# eb-1.net
KiCad netlist of a schematic drawn in EAGLE
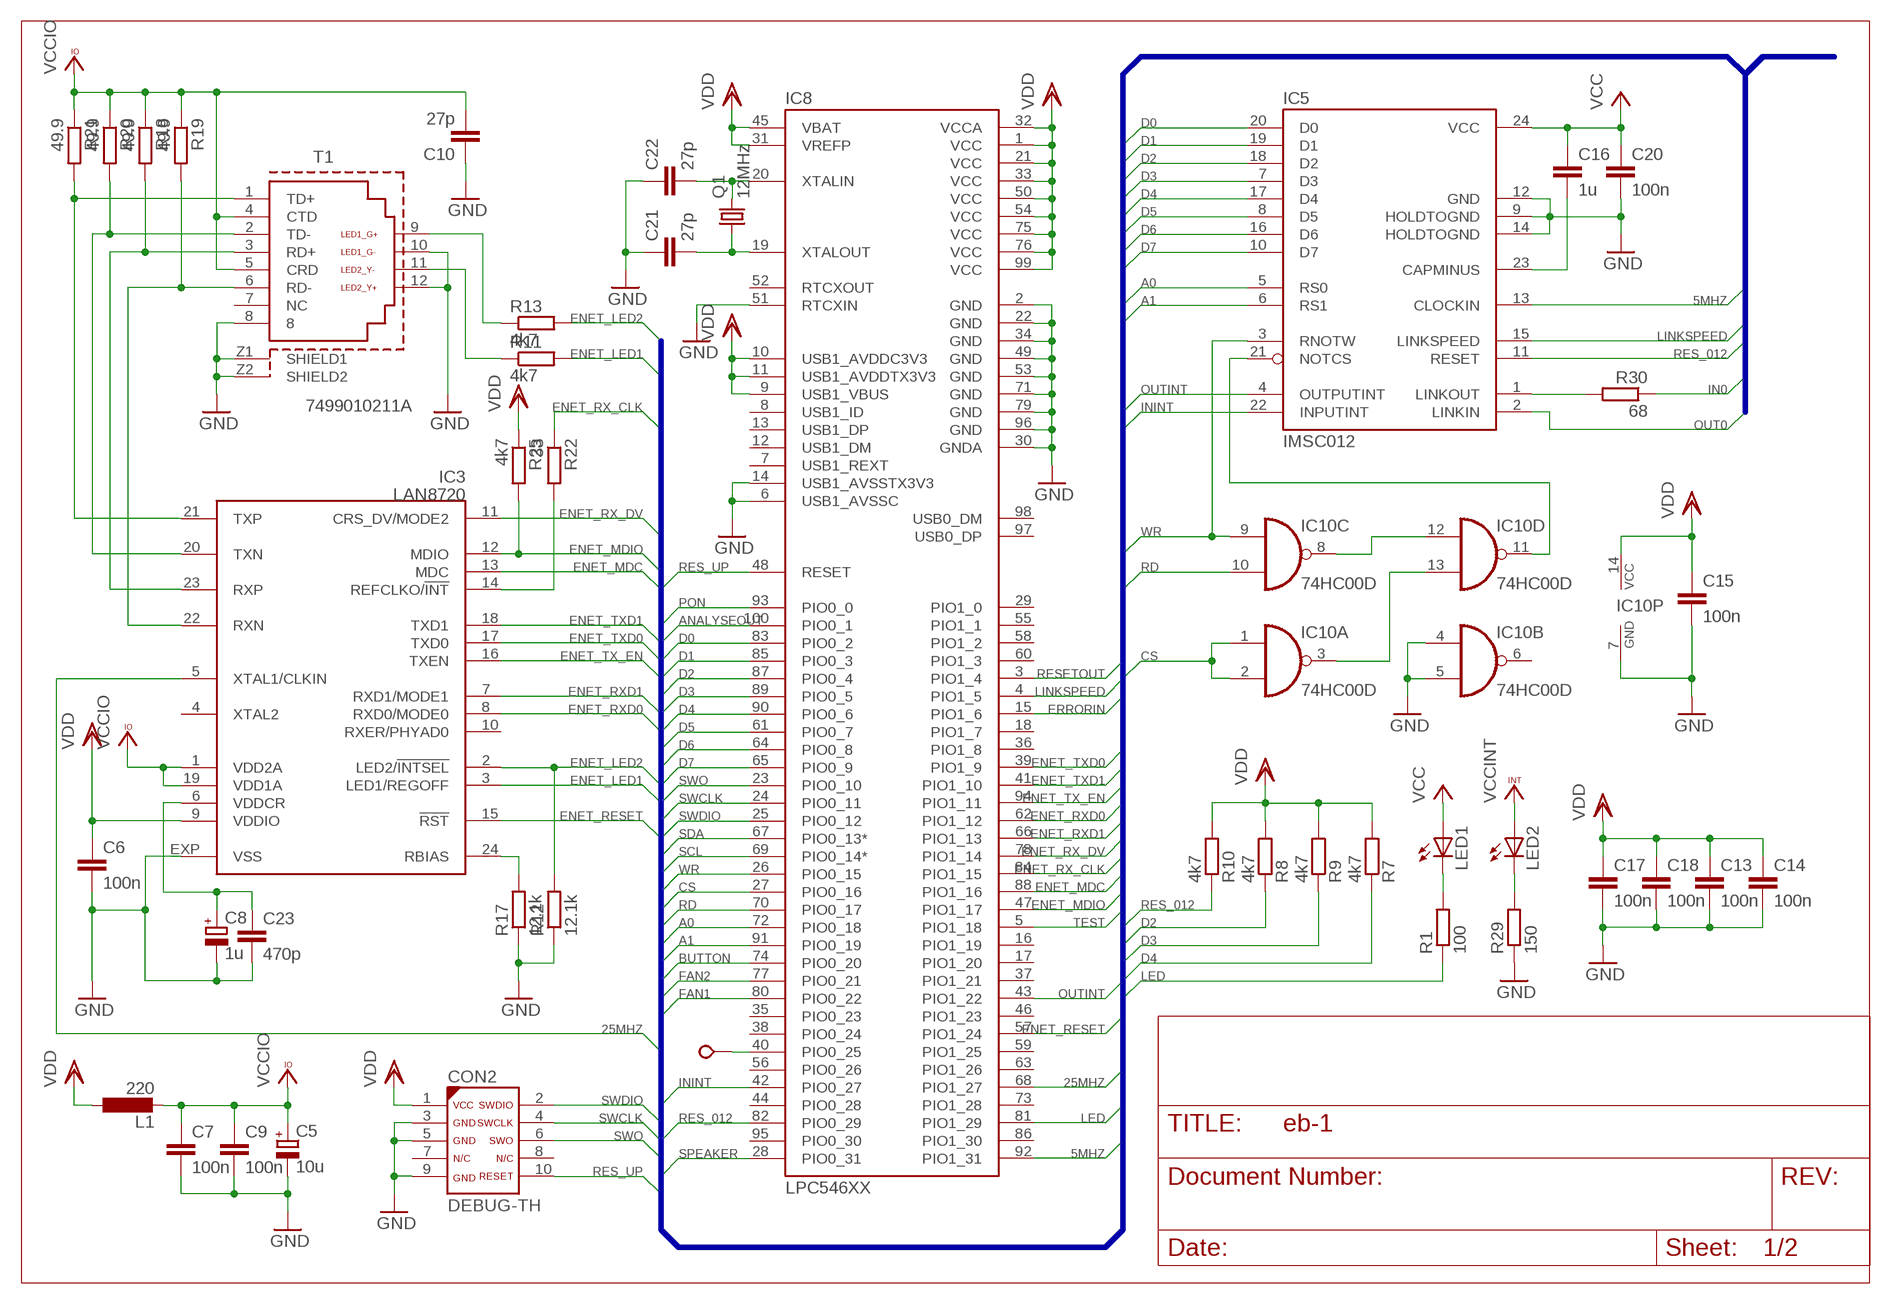
[diagram p0: schematic, sheet 1]
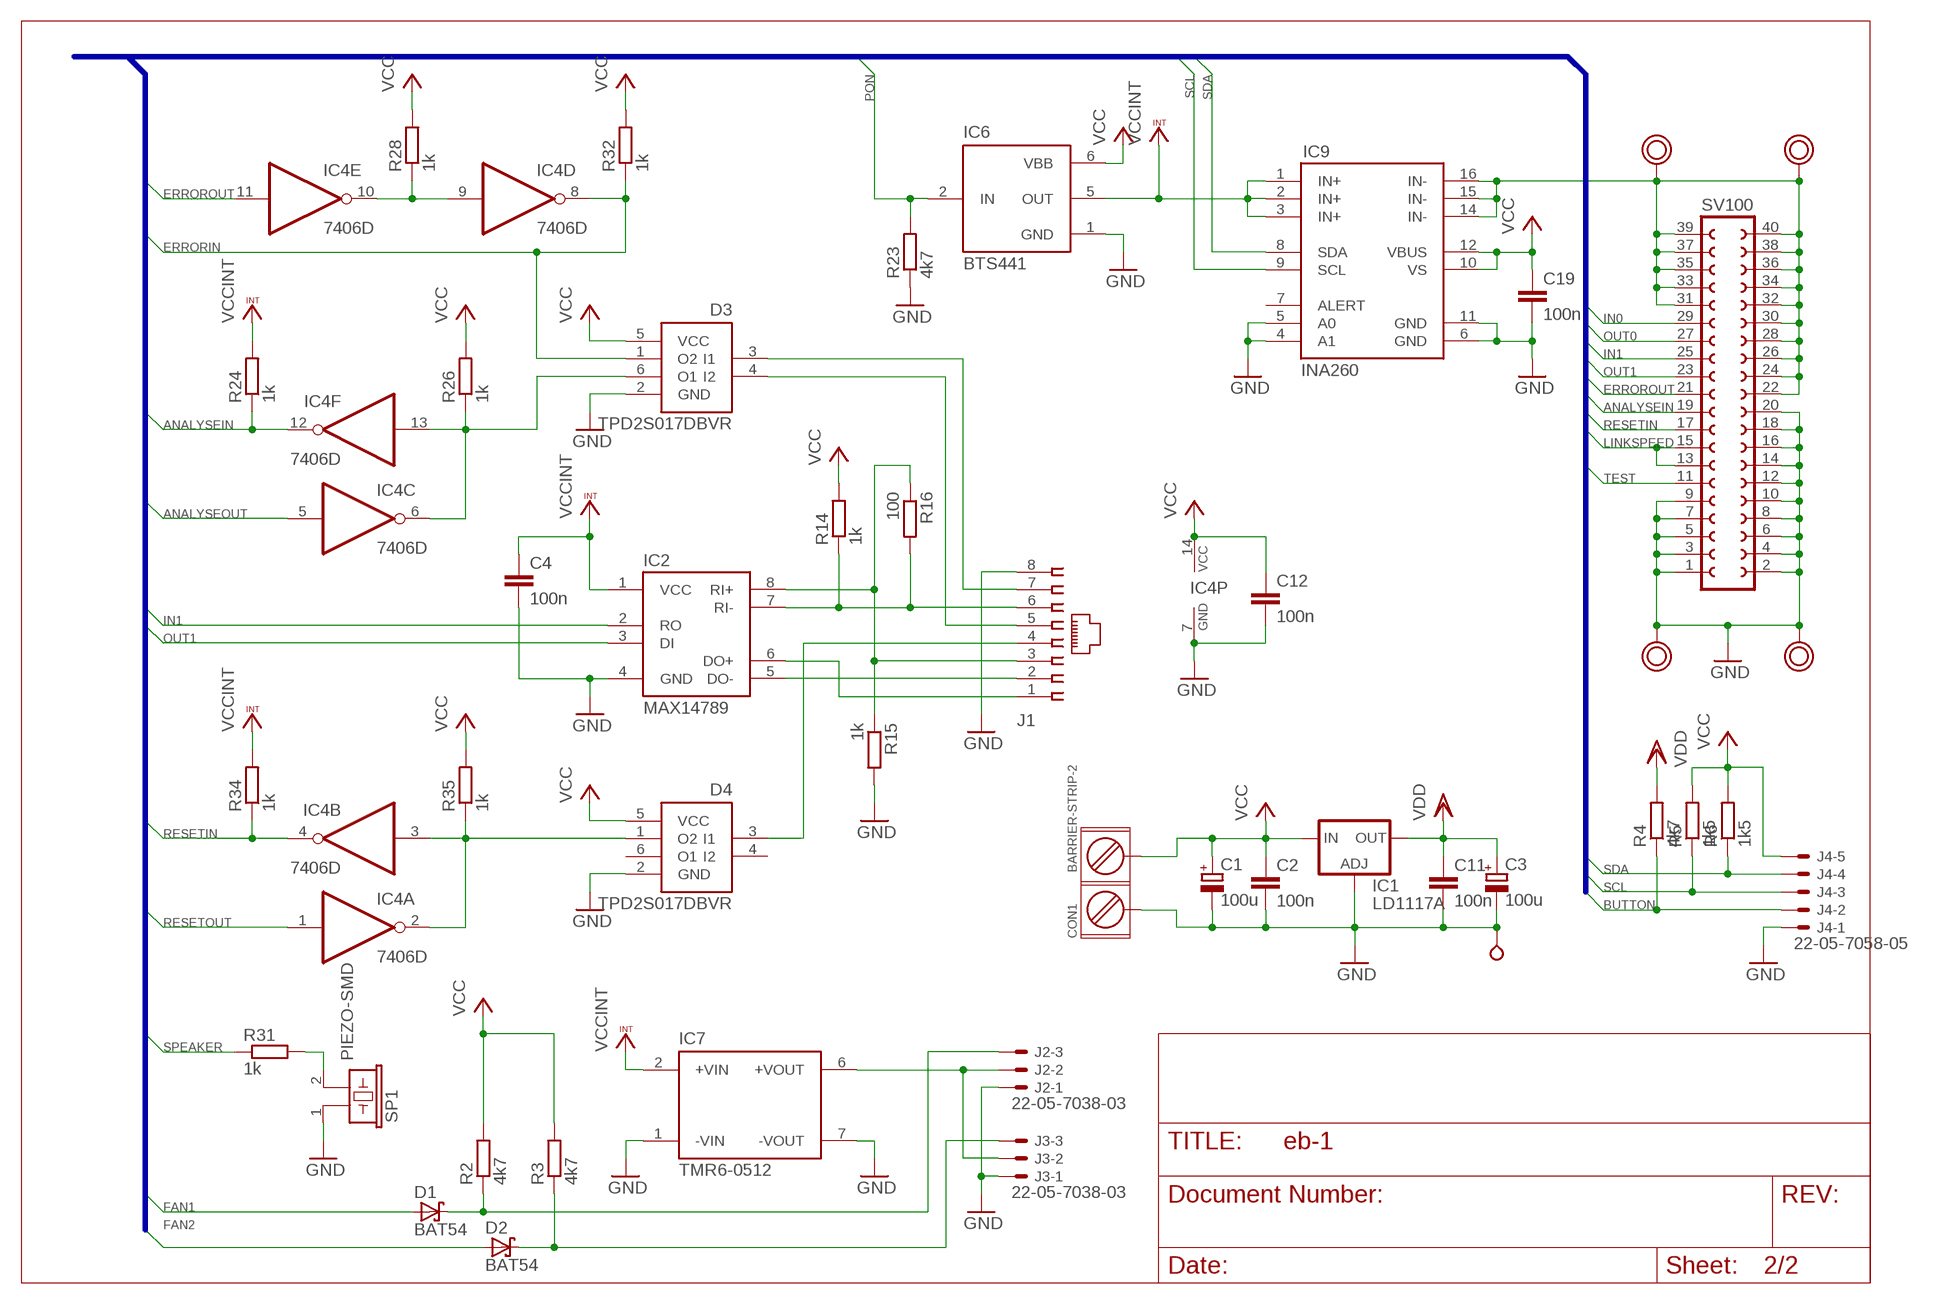
[diagram p1: schematic, sheet 2]

(export (version "E")
  (design (tool "Eeschema 10.0.6"))
  (components
    (comp (ref "C1")
      (value "100u")
      (footprint "eagle-import:SMC_B")
      (libsource (lib "eagle-import") (part "CPOL-EUSMCB"))
    )
    (comp (ref "C2")
      (value "100n")
      (footprint "eagle-import:C1206")
      (libsource (lib "eagle-import") (part "C-EUC1206"))
    )
    (comp (ref "C3")
      (value "100u")
      (footprint "eagle-import:SMC_B")
      (libsource (lib "eagle-import") (part "CPOL-EUSMCB"))
    )
    (comp (ref "C4")
      (value "100n")
      (footprint "eagle-import:C1206")
      (libsource (lib "eagle-import") (part "C-EUC1206"))
    )
    (comp (ref "C11")
      (value "100n")
      (footprint "eagle-import:C1206")
      (libsource (lib "eagle-import") (part "C-EUC1206"))
    )
    (comp (ref "C12")
      (value "100n")
      (footprint "eagle-import:C1206")
      (libsource (lib "eagle-import") (part "C-EUC1206"))
    )
    (comp (ref "C19")
      (value "100n")
      (footprint "eagle-import:C1206")
      (libsource (lib "eagle-import") (part "C-EUC1206"))
    )
    (comp (ref "CON1")
      (value "BARRIER-STRIP-2")
      (footprint "eagle-import:BARRIER-STRIP-2")
      (libsource (lib "eagle-import") (part "BARRIER-STRIP-2"))
    )
    (comp (ref "D1")
      (value "BAT54")
      (footprint "eagle-import:SOT23")
      (libsource (lib "eagle-import") (part "BAT54"))
    )
    (comp (ref "D2")
      (value "BAT54")
      (footprint "eagle-import:SOT23")
      (libsource (lib "eagle-import") (part "BAT54"))
    )
    (comp (ref "D3")
      (value "TPD2S017DBVR")
      (footprint "eagle-import:SOT23-6")
      (libsource (lib "eagle-import") (part "TPD2S017DBVR"))
    )
    (comp (ref "D4")
      (value "TPD2S017DBVR")
      (footprint "eagle-import:SOT23-6")
      (libsource (lib "eagle-import") (part "TPD2S017DBVR"))
    )
    (comp (ref "IC1")
      (value "LD1117A")
      (footprint "eagle-import:SOT223")
      (libsource (lib "eagle-import") (part "LD1117A"))
    )
    (comp (ref "IC2")
      (value "MAX14789")
      (footprint "eagle-import:SO8")
      (libsource (lib "eagle-import") (part "DS8921"))
    )
    (comp (ref "IC4")
      (value "7406D")
      (footprint "eagle-import:SO14")
      (libsource (lib "eagle-import") (part "7406D"))
    )
    (comp (ref "IC6")
      (value "BTS441")
      (footprint "eagle-import:TO263-4")
      (libsource (lib "eagle-import") (part "BTS441"))
    )
    (comp (ref "IC7")
      (value "TMR6-0512")
      (footprint "eagle-import:TMR6-0512")
      (libsource (lib "eagle-import") (part "TMR6-0512"))
    )
    (comp (ref "IC9")
      (value "INA260")
      (footprint "eagle-import:TSSOP-16")
      (libsource (lib "eagle-import") (part "INA260"))
    )
    (comp (ref "J1")
      (value "555164-1")
      (footprint "eagle-import:555164-1")
      (libsource (lib "eagle-import") (part "555164-1"))
    )
    (comp (ref "J2")
      (value "22-05-7038-03")
      (footprint "eagle-import:7395-03")
      (fields (field (name "DIGIKEY") "WM2785-ND"))
      (libsource (lib "eagle-import") (part "22-?-0305-7038"))
    )
    (comp (ref "J3")
      (value "22-05-7038-03")
      (footprint "eagle-import:7395-03")
      (fields (field (name "DIGIKEY") "WM2785-ND"))
      (libsource (lib "eagle-import") (part "22-?-0305-7038"))
    )
    (comp (ref "J4")
      (value "22-05-7058-05")
      (footprint "eagle-import:7395-05")
      (fields (field (name "DIGIKEY") "WM2787-ND"))
      (libsource (lib "eagle-import") (part "22-?-0505-7058"))
    )
    (comp (ref "R2")
      (value "4k7")
      (footprint "eagle-import:R1206")
      (libsource (lib "eagle-import") (part "R-EU_R1206"))
    )
    (comp (ref "R3")
      (value "4k7")
      (footprint "eagle-import:R1206")
      (libsource (lib "eagle-import") (part "R-EU_R1206"))
    )
    (comp (ref "R4")
      (value "4k7")
      (footprint "eagle-import:R1206")
      (libsource (lib "eagle-import") (part "R-EU_R1206"))
    )
    (comp (ref "R5")
      (value "1k5")
      (footprint "eagle-import:R1206")
      (libsource (lib "eagle-import") (part "R-EU_R1206"))
    )
    (comp (ref "R6")
      (value "1k5")
      (footprint "eagle-import:R1206")
      (libsource (lib "eagle-import") (part "R-EU_R1206"))
    )
    (comp (ref "R14")
      (value "1k")
      (footprint "eagle-import:R1206")
      (libsource (lib "eagle-import") (part "R-EU_R1206"))
    )
    (comp (ref "R15")
      (value "1k")
      (footprint "eagle-import:R1206")
      (libsource (lib "eagle-import") (part "R-EU_R1206"))
    )
    (comp (ref "R16")
      (value "100")
      (footprint "eagle-import:R1206")
      (libsource (lib "eagle-import") (part "R-EU_R1206"))
    )
    (comp (ref "R23")
      (value "4k7")
      (footprint "eagle-import:R1206")
      (libsource (lib "eagle-import") (part "R-EU_R1206"))
    )
    (comp (ref "R24")
      (value "1k")
      (footprint "eagle-import:R1206")
      (libsource (lib "eagle-import") (part "R-EU_R1206"))
    )
    (comp (ref "R26")
      (value "1k")
      (footprint "eagle-import:R1206")
      (libsource (lib "eagle-import") (part "R-EU_R1206"))
    )
    (comp (ref "R28")
      (value "1k")
      (footprint "eagle-import:R1206")
      (libsource (lib "eagle-import") (part "R-EU_R1206"))
    )
    (comp (ref "R31")
      (value "1k")
      (footprint "eagle-import:R1206")
      (libsource (lib "eagle-import") (part "R-EU_R1206"))
    )
    (comp (ref "R32")
      (value "1k")
      (footprint "eagle-import:R1206")
      (libsource (lib "eagle-import") (part "R-EU_R1206"))
    )
    (comp (ref "R34")
      (value "1k")
      (footprint "eagle-import:R1206")
      (libsource (lib "eagle-import") (part "R-EU_R1206"))
    )
    (comp (ref "R35")
      (value "1k")
      (footprint "eagle-import:R1206")
      (libsource (lib "eagle-import") (part "R-EU_R1206"))
    )
    (comp (ref "SCREW1")
      (value "POWERPAD")
      (footprint "eagle-import:POWERPAD")
      (libsource (lib "eagle-import") (part "POWERPAD"))
    )
    (comp (ref "SCREW2")
      (value "POWERPAD")
      (footprint "eagle-import:POWERPAD")
      (libsource (lib "eagle-import") (part "POWERPAD"))
    )
    (comp (ref "SCREW3")
      (value "POWERPAD")
      (footprint "eagle-import:POWERPAD")
      (libsource (lib "eagle-import") (part "POWERPAD"))
    )
    (comp (ref "SCREW4")
      (value "POWERPAD")
      (footprint "eagle-import:POWERPAD")
      (libsource (lib "eagle-import") (part "POWERPAD"))
    )
    (comp (ref "SP1")
      (value "PIEZO-SMD")
      (footprint "eagle-import:PIEZO-SMD")
      (libsource (lib "eagle-import") (part "PIEZO-SMD"))
    )
    (comp (ref "SV100")
      (value "FE20-2")
      (footprint "eagle-import:FE20-2")
      (libsource (lib "eagle-import") (part "FE20-2"))
    )
    (comp (ref "TP1")
      (value "TESTPOINT")
      (footprint "eagle-import:VERO_TP")
      (libsource (lib "eagle-import") (part "TESTPOINT"))
    )
    (comp (ref "C5")
      (value "10u")
      (footprint "eagle-import:CT3216")
      (libsource (lib "eagle-import") (part "CPOL-EUCT3216"))
    )
    (comp (ref "C6")
      (value "100n")
      (footprint "eagle-import:C1206")
      (libsource (lib "eagle-import") (part "C-EUC1206"))
    )
    (comp (ref "C7")
      (value "100n")
      (footprint "eagle-import:C1206")
      (libsource (lib "eagle-import") (part "C-EUC1206"))
    )
    (comp (ref "C8")
      (value "1u")
      (footprint "eagle-import:CT3216")
      (libsource (lib "eagle-import") (part "CPOL-EUCT3216"))
    )
    (comp (ref "C9")
      (value "100n")
      (footprint "eagle-import:C1206")
      (libsource (lib "eagle-import") (part "C-EUC1206"))
    )
    (comp (ref "C10")
      (value "27p")
      (footprint "eagle-import:C1206")
      (libsource (lib "eagle-import") (part "C-EUC1206"))
    )
    (comp (ref "C13")
      (value "100n")
      (footprint "eagle-import:C1206")
      (libsource (lib "eagle-import") (part "C-EUC1206"))
    )
    (comp (ref "C14")
      (value "100n")
      (footprint "eagle-import:C1206")
      (libsource (lib "eagle-import") (part "C-EUC1206"))
    )
    (comp (ref "C15")
      (value "100n")
      (footprint "eagle-import:C1206")
      (libsource (lib "eagle-import") (part "C-EUC1206"))
    )
    (comp (ref "C16")
      (value "1u")
      (footprint "eagle-import:C1206")
      (libsource (lib "eagle-import") (part "C-EUC1206"))
    )
    (comp (ref "C17")
      (value "100n")
      (footprint "eagle-import:C1206")
      (libsource (lib "eagle-import") (part "C-EUC1206"))
    )
    (comp (ref "C18")
      (value "100n")
      (footprint "eagle-import:C1206")
      (libsource (lib "eagle-import") (part "C-EUC1206"))
    )
    (comp (ref "C20")
      (value "100n")
      (footprint "eagle-import:C1206")
      (libsource (lib "eagle-import") (part "C-EUC1206"))
    )
    (comp (ref "C21")
      (value "27p")
      (footprint "eagle-import:C1206")
      (libsource (lib "eagle-import") (part "C-EUC1206"))
    )
    (comp (ref "C22")
      (value "27p")
      (footprint "eagle-import:C1206")
      (libsource (lib "eagle-import") (part "C-EUC1206"))
    )
    (comp (ref "C23")
      (value "470p")
      (footprint "eagle-import:C1206")
      (libsource (lib "eagle-import") (part "C-EUC1206"))
    )
    (comp (ref "CON2")
      (value "DEBUG-TH")
      (footprint "eagle-import:DEBUG-TH")
      (libsource (lib "eagle-import") (part "DEBUG-TH"))
    )
    (comp (ref "IC3")
      (value "LAN8720")
      (footprint "eagle-import:QFN24")
      (libsource (lib "eagle-import") (part "LAN8720"))
    )
    (comp (ref "IC5")
      (value "IMSC012")
      (footprint "eagle-import:DIL24-3")
      (libsource (lib "eagle-import") (part "IMSC012"))
    )
    (comp (ref "IC8")
      (value "LPC546XX")
      (footprint "eagle-import:LQFP100")
      (libsource (lib "eagle-import") (part "LPC546XX"))
    )
    (comp (ref "IC10")
      (value "74HC00D")
      (footprint "eagle-import:SO14")
      (libsource (lib "eagle-import") (part "7400DHC"))
    )
    (comp (ref "L1")
      (value "220")
      (footprint "eagle-import:L3216C")
      (libsource (lib "eagle-import") (part "L-EUL3216C"))
    )
    (comp (ref "LED1")
      (value "LEDSMT1206")
      (footprint "eagle-import:1206")
      (libsource (lib "eagle-import") (part "LEDSMT1206"))
    )
    (comp (ref "LED2")
      (value "LEDSMT1206")
      (footprint "eagle-import:1206")
      (libsource (lib "eagle-import") (part "LEDSMT1206"))
    )
    (comp (ref "Q1")
      (value "12MHz")
      (footprint "eagle-import:HC49UP")
      (libsource (lib "eagle-import") (part "CRYSTALHC49UP"))
    )
    (comp (ref "R1")
      (value "100")
      (footprint "eagle-import:R1206")
      (libsource (lib "eagle-import") (part "R-EU_R1206"))
    )
    (comp (ref "R7")
      (value "4k7")
      (footprint "eagle-import:R1206")
      (libsource (lib "eagle-import") (part "R-EU_R1206"))
    )
    (comp (ref "R8")
      (value "4k7")
      (footprint "eagle-import:R1206")
      (libsource (lib "eagle-import") (part "R-EU_R1206"))
    )
    (comp (ref "R9")
      (value "4k7")
      (footprint "eagle-import:R1206")
      (libsource (lib "eagle-import") (part "R-EU_R1206"))
    )
    (comp (ref "R10")
      (value "4k7")
      (footprint "eagle-import:R1206")
      (libsource (lib "eagle-import") (part "R-EU_R1206"))
    )
    (comp (ref "R11")
      (value "4k7")
      (footprint "eagle-import:R1206")
      (libsource (lib "eagle-import") (part "R-EU_R1206"))
    )
    (comp (ref "R12")
      (value "12.1k")
      (footprint "eagle-import:R1206")
      (libsource (lib "eagle-import") (part "R-EU_R1206"))
    )
    (comp (ref "R13")
      (value "4k7")
      (footprint "eagle-import:R1206")
      (libsource (lib "eagle-import") (part "R-EU_R1206"))
    )
    (comp (ref "R17")
      (value "12.1k")
      (footprint "eagle-import:R1206")
      (libsource (lib "eagle-import") (part "R-EU_R1206"))
    )
    (comp (ref "R18")
      (value "49.9")
      (footprint "eagle-import:R1206")
      (libsource (lib "eagle-import") (part "R-EU_R1206"))
    )
    (comp (ref "R19")
      (value "49.9")
      (footprint "eagle-import:R1206")
      (libsource (lib "eagle-import") (part "R-EU_R1206"))
    )
    (comp (ref "R20")
      (value "49.9")
      (footprint "eagle-import:R1206")
      (libsource (lib "eagle-import") (part "R-EU_R1206"))
    )
    (comp (ref "R21")
      (value "49.9")
      (footprint "eagle-import:R1206")
      (libsource (lib "eagle-import") (part "R-EU_R1206"))
    )
    (comp (ref "R22")
      (value "33")
      (footprint "eagle-import:R1206")
      (libsource (lib "eagle-import") (part "R-EU_R1206"))
    )
    (comp (ref "R25")
      (value "4k7")
      (footprint "eagle-import:R1206")
      (libsource (lib "eagle-import") (part "R-EU_R1206"))
    )
    (comp (ref "R29")
      (value "150")
      (footprint "eagle-import:R1206")
      (libsource (lib "eagle-import") (part "R-EU_R1206"))
    )
    (comp (ref "R30")
      (value "68")
      (footprint "eagle-import:R1206")
      (libsource (lib "eagle-import") (part "R-EU_R1206"))
    )
    (comp (ref "T1")
      (value "7499010211A")
      (footprint "eagle-import:7499010211A")
      (libsource (lib "eagle-import") (part "WE-RJ45_7499010211A"))
    )
    (comp (ref "TP2")
      (value "TESTPOINT")
      (footprint "eagle-import:VERO_TP")
      (libsource (lib "eagle-import") (part "TESTPOINT"))
    )
  )
  (nets
    (net (code "1") (name "5MHZ") (class "Default")
      (node (ref "IC5") (pin "13") (pinfunction "CLOCKIN_13") (pintype "input"))
      (node (ref "IC8") (pin "92") (pinfunction "PIO1_31_92") (pintype "tri_state"))
    )
    (net (code "2") (name "25MHZ") (class "Default")
      (node (ref "IC3") (pin "5") (pinfunction "XTAL1/CLKIN_5") (pintype "bidirectional"))
      (node (ref "IC8") (pin "68") (pinfunction "PIO1_27_68") (pintype "tri_state"))
    )
    (net (code "3") (name "A0") (class "Default")
      (node (ref "IC5") (pin "5") (pinfunction "RS0_5") (pintype "input"))
      (node (ref "IC8") (pin "72") (pinfunction "PIO0_18_72") (pintype "tri_state"))
    )
    (net (code "4") (name "A1") (class "Default")
      (node (ref "IC5") (pin "6") (pinfunction "RS1_6") (pintype "input"))
      (node (ref "IC8") (pin "91") (pinfunction "PIO0_19_91") (pintype "tri_state"))
    )
    (net (code "5") (name "ANALYSEIN") (class "Default")
      (node (ref "IC4") (pin "12") (pinfunction "O_12") (pintype "open_collector"))
      (node (ref "R24") (pin "1") (pinfunction "1_1") (pintype "passive"))
      (node (ref "SV100") (pin "19") (pinfunction "19_19") (pintype "passive"))
    )
    (net (code "6") (name "ANALYSEOUT") (class "Default")
      (node (ref "IC4") (pin "5") (pinfunction "I_5") (pintype "input"))
      (node (ref "IC8") (pin "100") (pinfunction "PIO0_1_100") (pintype "tri_state"))
    )
    (net (code "7") (name "BUTTON") (class "Default")
      (node (ref "IC8") (pin "74") (pinfunction "PIO0_20_74") (pintype "tri_state"))
      (node (ref "J4") (pin "2") (pinfunction "S_2") (pintype "passive"))
      (node (ref "R4") (pin "1") (pinfunction "1_1") (pintype "passive"))
    )
    (net (code "8") (name "CS") (class "Default")
      (node (ref "IC10") (pin "1") (pinfunction "I0_1") (pintype "input"))
      (node (ref "IC10") (pin "2") (pinfunction "I1_2") (pintype "input"))
      (node (ref "IC8") (pin "27") (pinfunction "PIO0_16_27") (pintype "tri_state"))
    )
    (net (code "9") (name "D0") (class "Default")
      (node (ref "IC5") (pin "20") (pinfunction "D0_20") (pintype "bidirectional"))
      (node (ref "IC8") (pin "83") (pinfunction "PIO0_2_83") (pintype "tri_state"))
    )
    (net (code "10") (name "D1") (class "Default")
      (node (ref "IC5") (pin "19") (pinfunction "D1_19") (pintype "bidirectional"))
      (node (ref "IC8") (pin "85") (pinfunction "PIO0_3_85") (pintype "tri_state"))
    )
    (net (code "11") (name "D2") (class "Default")
      (node (ref "IC5") (pin "18") (pinfunction "D2_18") (pintype "bidirectional"))
      (node (ref "IC8") (pin "87") (pinfunction "PIO0_4_87") (pintype "tri_state"))
      (node (ref "R8") (pin "1") (pinfunction "1_1") (pintype "passive"))
    )
    (net (code "12") (name "D3") (class "Default")
      (node (ref "IC5") (pin "7") (pinfunction "D3_7") (pintype "bidirectional"))
      (node (ref "IC8") (pin "89") (pinfunction "PIO0_5_89") (pintype "tri_state"))
      (node (ref "R9") (pin "1") (pinfunction "1_1") (pintype "passive"))
    )
    (net (code "13") (name "D4") (class "Default")
      (node (ref "IC5") (pin "17") (pinfunction "D4_17") (pintype "bidirectional"))
      (node (ref "IC8") (pin "90") (pinfunction "PIO0_6_90") (pintype "tri_state"))
      (node (ref "R7") (pin "1") (pinfunction "1_1") (pintype "passive"))
    )
    (net (code "14") (name "D5") (class "Default")
      (node (ref "IC5") (pin "8") (pinfunction "D5_8") (pintype "bidirectional"))
      (node (ref "IC8") (pin "61") (pinfunction "PIO0_7_61") (pintype "tri_state"))
    )
    (net (code "15") (name "D6") (class "Default")
      (node (ref "IC5") (pin "16") (pinfunction "D6_16") (pintype "bidirectional"))
      (node (ref "IC8") (pin "64") (pinfunction "PIO0_8_64") (pintype "tri_state"))
    )
    (net (code "16") (name "D7") (class "Default")
      (node (ref "IC5") (pin "10") (pinfunction "D7_10") (pintype "bidirectional"))
      (node (ref "IC8") (pin "65") (pinfunction "PIO0_9_65") (pintype "tri_state"))
    )
    (net (code "17") (name "ENET_LED1") (class "Default")
      (node (ref "IC3") (pin "3") (pinfunction "LED1/REGOFF_3") (pintype "bidirectional"))
      (node (ref "R11") (pin "2") (pinfunction "2_2") (pintype "passive"))
    )
    (net (code "18") (name "ENET_LED2") (class "Default")
      (node (ref "IC3") (pin "2") (pinfunction "LED2/~{INTSEL}_2") (pintype "bidirectional"))
      (node (ref "R12") (pin "2") (pinfunction "2_2") (pintype "passive"))
      (node (ref "R13") (pin "2") (pinfunction "2_2") (pintype "passive"))
    )
    (net (code "19") (name "ENET_MDC") (class "Default")
      (node (ref "IC3") (pin "13") (pinfunction "MDC_13") (pintype "bidirectional"))
      (node (ref "IC8") (pin "88") (pinfunction "PIO1_16_88") (pintype "tri_state"))
    )
    (net (code "20") (name "ENET_MDIO") (class "Default")
      (node (ref "IC3") (pin "12") (pinfunction "MDIO_12") (pintype "bidirectional"))
      (node (ref "IC8") (pin "47") (pinfunction "PIO1_17_47") (pintype "tri_state"))
      (node (ref "R25") (pin "2") (pinfunction "2_2") (pintype "passive"))
    )
    (net (code "21") (name "ENET_RESET") (class "Default")
      (node (ref "IC3") (pin "15") (pinfunction "~{RST}_15") (pintype "bidirectional"))
      (node (ref "IC8") (pin "57") (pinfunction "PIO1_24_57") (pintype "tri_state"))
    )
    (net (code "22") (name "ENET_RXD0") (class "Default")
      (node (ref "IC3") (pin "8") (pinfunction "RXD0/MODE0_8") (pintype "bidirectional"))
      (node (ref "IC8") (pin "62") (pinfunction "PIO1_12_62") (pintype "tri_state"))
    )
    (net (code "23") (name "ENET_RXD1") (class "Default")
      (node (ref "IC3") (pin "7") (pinfunction "RXD1/MODE1_7") (pintype "bidirectional"))
      (node (ref "IC8") (pin "66") (pinfunction "PIO1_13_66") (pintype "tri_state"))
    )
    (net (code "24") (name "ENET_RX_CLK") (class "Default")
      (node (ref "IC8") (pin "84") (pinfunction "PIO1_15_84") (pintype "tri_state"))
      (node (ref "R22") (pin "1") (pinfunction "1_1") (pintype "passive"))
    )
    (net (code "25") (name "ENET_RX_DV") (class "Default")
      (node (ref "IC3") (pin "11") (pinfunction "CRS_DV/MODE2_11") (pintype "bidirectional"))
      (node (ref "IC8") (pin "78") (pinfunction "PIO1_14_78") (pintype "tri_state"))
    )
    (net (code "26") (name "ENET_TXD0") (class "Default")
      (node (ref "IC3") (pin "17") (pinfunction "TXD0_17") (pintype "bidirectional"))
      (node (ref "IC8") (pin "39") (pinfunction "PIO1_9_39") (pintype "tri_state"))
    )
    (net (code "27") (name "ENET_TXD1") (class "Default")
      (node (ref "IC3") (pin "18") (pinfunction "TXD1_18") (pintype "bidirectional"))
      (node (ref "IC8") (pin "41") (pinfunction "PIO1_10_41") (pintype "tri_state"))
    )
    (net (code "28") (name "ENET_TX_EN") (class "Default")
      (node (ref "IC3") (pin "16") (pinfunction "TXEN_16") (pintype "bidirectional"))
      (node (ref "IC8") (pin "94") (pinfunction "PIO1_11_94") (pintype "tri_state"))
    )
    (net (code "29") (name "ERRORIN") (class "Default")
      (node (ref "D3") (pin "1") (pinfunction "O2_1") (pintype "passive"))
      (node (ref "IC4") (pin "8") (pinfunction "O_8") (pintype "open_collector"))
      (node (ref "IC8") (pin "15") (pinfunction "PIO1_6_15") (pintype "tri_state"))
      (node (ref "R32") (pin "1") (pinfunction "1_1") (pintype "passive"))
    )
    (net (code "30") (name "ERROROUT") (class "Default")
      (node (ref "IC4") (pin "11") (pinfunction "I_11") (pintype "input"))
      (node (ref "SV100") (pin "21") (pinfunction "21_21") (pintype "passive"))
    )
    (net (code "31") (name "FAN1") (class "Default")
      (node (ref "D1") (pin "1") (pinfunction "A_1") (pintype "passive"))
      (node (ref "IC8") (pin "80") (pinfunction "PIO0_22_80") (pintype "tri_state"))
    )
    (net (code "32") (name "FAN2") (class "Default")
      (node (ref "D2") (pin "1") (pinfunction "A_1") (pintype "passive"))
      (node (ref "IC8") (pin "77") (pinfunction "PIO0_21_77") (pintype "tri_state"))
    )
    (net (code "33") (name "GND") (class "Default")
      (node (ref "C1") (pin "-") (pinfunction "-_-") (pintype "passive"))
      (node (ref "C10") (pin "1") (pinfunction "1_1") (pintype "passive"))
      (node (ref "C11") (pin "2") (pinfunction "2_2") (pintype "passive"))
      (node (ref "C12") (pin "2") (pinfunction "2_2") (pintype "passive"))
      (node (ref "C13") (pin "2") (pinfunction "2_2") (pintype "passive"))
      (node (ref "C14") (pin "2") (pinfunction "2_2") (pintype "passive"))
      (node (ref "C15") (pin "2") (pinfunction "2_2") (pintype "passive"))
      (node (ref "C17") (pin "2") (pinfunction "2_2") (pintype "passive"))
      (node (ref "C18") (pin "2") (pinfunction "2_2") (pintype "passive"))
      (node (ref "C19") (pin "2") (pinfunction "2_2") (pintype "passive"))
      (node (ref "C2") (pin "2") (pinfunction "2_2") (pintype "passive"))
      (node (ref "C20") (pin "2") (pinfunction "2_2") (pintype "passive"))
      (node (ref "C21") (pin "1") (pinfunction "1_1") (pintype "passive"))
      (node (ref "C22") (pin "1") (pinfunction "1_1") (pintype "passive"))
      (node (ref "C23") (pin "2") (pinfunction "2_2") (pintype "passive"))
      (node (ref "C3") (pin "-") (pinfunction "-_-") (pintype "passive"))
      (node (ref "C4") (pin "2") (pinfunction "2_2") (pintype "passive"))
      (node (ref "C5") (pin "-") (pinfunction "-_-") (pintype "passive"))
      (node (ref "C6") (pin "2") (pinfunction "2_2") (pintype "passive"))
      (node (ref "C7") (pin "2") (pinfunction "2_2") (pintype "passive"))
      (node (ref "C8") (pin "-") (pinfunction "-_-") (pintype "passive"))
      (node (ref "C9") (pin "2") (pinfunction "2_2") (pintype "passive"))
      (node (ref "CON1") (pin "1") (pinfunction "1_1") (pintype "passive"))
      (node (ref "CON2") (pin "3") (pinfunction "3_3") (pintype "passive"))
      (node (ref "CON2") (pin "5") (pinfunction "5_5") (pintype "passive"))
      (node (ref "CON2") (pin "9") (pinfunction "9_9") (pintype "passive"))
      (node (ref "D3") (pin "2") (pinfunction "GND_2") (pintype "passive"))
      (node (ref "D4") (pin "2") (pinfunction "GND_2") (pintype "passive"))
      (node (ref "IC1") (pin "1") (pinfunction "ADJ_1") (pintype "input"))
      (node (ref "IC10") (pin "4") (pinfunction "I0_4") (pintype "input"))
      (node (ref "IC10") (pin "5") (pinfunction "I1_5") (pintype "input"))
      (node (ref "IC10") (pin "7") (pinfunction "GND_7") (pintype "power_in"))
      (node (ref "IC2") (pin "4") (pinfunction "GND_4") (pintype "power_in"))
      (node (ref "IC3") (pin "EXP") (pinfunction "VSS_EXP") (pintype "power_in"))
      (node (ref "IC4") (pin "7") (pinfunction "GND_7") (pintype "power_in"))
      (node (ref "IC5") (pin "12") (pinfunction "GND_12") (pintype "power_in"))
      (node (ref "IC5") (pin "14") (pinfunction "HOLDTOGND_14") (pintype "input"))
      (node (ref "IC5") (pin "9") (pinfunction "HOLDTOGND_9") (pintype "input"))
      (node (ref "IC6") (pin "1") (pinfunction "GND_1") (pintype "power_in"))
      (node (ref "IC7") (pin "1") (pinfunction "-VIN_1") (pintype "passive"))
      (node (ref "IC7") (pin "7") (pinfunction "-VOUT_7") (pintype "passive"))
      (node (ref "IC8") (pin "14") (pinfunction "USB1_AVSSTX3V3_14") (pintype "tri_state"))
      (node (ref "IC8") (pin "2") (pinfunction "GND_2") (pintype "power_in"))
      (node (ref "IC8") (pin "22") (pinfunction "GND_22") (pintype "power_in"))
      (node (ref "IC8") (pin "30") (pinfunction "GNDA_30") (pintype "power_in"))
      (node (ref "IC8") (pin "34") (pinfunction "GND_34") (pintype "power_in"))
      (node (ref "IC8") (pin "49") (pinfunction "GND_49") (pintype "power_in"))
      (node (ref "IC8") (pin "51") (pinfunction "RTCXIN_51") (pintype "tri_state"))
      (node (ref "IC8") (pin "53") (pinfunction "GND_53") (pintype "power_in"))
      (node (ref "IC8") (pin "6") (pinfunction "USB1_AVSSC_6") (pintype "tri_state"))
      (node (ref "IC8") (pin "71") (pinfunction "GND_71") (pintype "power_in"))
      (node (ref "IC8") (pin "79") (pinfunction "GND_79") (pintype "power_in"))
      (node (ref "IC8") (pin "96") (pinfunction "GND_96") (pintype "power_in"))
      (node (ref "IC9") (pin "11") (pinfunction "GND_11") (pintype "power_in"))
      (node (ref "IC9") (pin "4") (pinfunction "A1_4") (pintype "input"))
      (node (ref "IC9") (pin "5") (pinfunction "A0_5") (pintype "input"))
      (node (ref "IC9") (pin "6") (pinfunction "GND_6") (pintype "power_in"))
      (node (ref "J1") (pin "8") (pinfunction "8_8") (pintype "passive"))
      (node (ref "J2") (pin "1") (pinfunction "S_1") (pintype "passive"))
      (node (ref "J3") (pin "1") (pinfunction "S_1") (pintype "passive"))
      (node (ref "J4") (pin "1") (pinfunction "S_1") (pintype "passive"))
      (node (ref "R12") (pin "1") (pinfunction "1_1") (pintype "passive"))
      (node (ref "R15") (pin "2") (pinfunction "2_2") (pintype "passive"))
      (node (ref "R17") (pin "1") (pinfunction "1_1") (pintype "passive"))
      (node (ref "R23") (pin "1") (pinfunction "1_1") (pintype "passive"))
      (node (ref "R29") (pin "1") (pinfunction "1_1") (pintype "passive"))
      (node (ref "SCREW2") (pin "P$1") (pinfunction "P$1_P$1") (pintype "bidirectional"))
      (node (ref "SCREW4") (pin "P$1") (pinfunction "P$1_P$1") (pintype "bidirectional"))
      (node (ref "SP1") (pin "1") (pinfunction "1_1") (pintype "passive"))
      (node (ref "SV100") (pin "1") (pinfunction "1_1") (pintype "passive"))
      (node (ref "SV100") (pin "10") (pinfunction "10_10") (pintype "passive"))
      (node (ref "SV100") (pin "12") (pinfunction "12_12") (pintype "passive"))
      (node (ref "SV100") (pin "14") (pinfunction "14_14") (pintype "passive"))
      (node (ref "SV100") (pin "16") (pinfunction "16_16") (pintype "passive"))
      (node (ref "SV100") (pin "18") (pinfunction "18_18") (pintype "passive"))
      (node (ref "SV100") (pin "2") (pinfunction "2_2") (pintype "passive"))
      (node (ref "SV100") (pin "20") (pinfunction "20_20") (pintype "passive"))
      (node (ref "SV100") (pin "3") (pinfunction "3_3") (pintype "passive"))
      (node (ref "SV100") (pin "4") (pinfunction "4_4") (pintype "passive"))
      (node (ref "SV100") (pin "5") (pinfunction "5_5") (pintype "passive"))
      (node (ref "SV100") (pin "6") (pinfunction "6_6") (pintype "passive"))
      (node (ref "SV100") (pin "7") (pinfunction "7_7") (pintype "passive"))
      (node (ref "SV100") (pin "8") (pinfunction "8_8") (pintype "passive"))
      (node (ref "SV100") (pin "9") (pinfunction "9_9") (pintype "passive"))
      (node (ref "T1") (pin "10") (pinfunction "LED1_G-_10") (pintype "passive"))
      (node (ref "T1") (pin "12") (pinfunction "LED2_Y+_12") (pintype "passive"))
      (node (ref "T1") (pin "8") (pinfunction "8_8") (pintype "passive"))
      (node (ref "T1") (pin "Z1") (pinfunction "SHIELD1_Z1") (pintype "passive"))
      (node (ref "T1") (pin "Z2") (pinfunction "SHIELD2_Z2") (pintype "passive"))
      (node (ref "TP1") (pin "P$1") (pinfunction "P$1_P$1") (pintype "passive"))
    )
    (net (code "34") (name "IN0") (class "Default")
      (node (ref "R30") (pin "1") (pinfunction "1_1") (pintype "passive"))
      (node (ref "SV100") (pin "29") (pinfunction "29_29") (pintype "passive"))
    )
    (net (code "35") (name "IN1") (class "Default")
      (node (ref "IC2") (pin "2") (pinfunction "RO_2") (pintype "output"))
      (node (ref "SV100") (pin "25") (pinfunction "25_25") (pintype "passive"))
    )
    (net (code "36") (name "ININT") (class "Default")
      (node (ref "IC5") (pin "22") (pinfunction "INPUTINT_22") (pintype "output"))
      (node (ref "IC8") (pin "42") (pinfunction "PIO0_27_42") (pintype "tri_state"))
    )
    (net (code "37") (name "LED") (class "Default")
      (node (ref "IC8") (pin "81") (pinfunction "PIO1_29_81") (pintype "tri_state"))
      (node (ref "R1") (pin "1") (pinfunction "1_1") (pintype "passive"))
    )
    (net (code "38") (name "LINKSPEED") (class "Default")
      (node (ref "IC5") (pin "15") (pinfunction "LINKSPEED_15") (pintype "input"))
      (node (ref "IC8") (pin "4") (pinfunction "PIO1_5_4") (pintype "tri_state"))
      (node (ref "SV100") (pin "13") (pinfunction "13_13") (pintype "passive"))
      (node (ref "SV100") (pin "15") (pinfunction "15_15") (pintype "passive"))
    )
    (net (code "39") (name "Net-(D1-C)") (class "Default")
      (node (ref "D1") (pin "3") (pinfunction "C_3") (pintype "passive"))
      (node (ref "J2") (pin "3") (pinfunction "S_3") (pintype "passive"))
      (node (ref "R2") (pin "1") (pinfunction "1_1") (pintype "passive"))
    )
    (net (code "40") (name "Net-(D2-C)") (class "Default")
      (node (ref "D2") (pin "3") (pinfunction "C_3") (pintype "passive"))
      (node (ref "J3") (pin "3") (pinfunction "S_3") (pintype "passive"))
      (node (ref "R3") (pin "1") (pinfunction "1_1") (pintype "passive"))
    )
    (net (code "41") (name "Net-(D3-I1)") (class "Default")
      (node (ref "D3") (pin "3") (pinfunction "I1_3") (pintype "passive"))
      (node (ref "J1") (pin "7") (pinfunction "7_7") (pintype "passive"))
    )
    (net (code "42") (name "Net-(D3-I2)") (class "Default")
      (node (ref "D3") (pin "4") (pinfunction "I2_4") (pintype "passive"))
      (node (ref "J1") (pin "5") (pinfunction "5_5") (pintype "passive"))
    )
    (net (code "43") (name "Net-(D3-O1)") (class "Default")
      (node (ref "D3") (pin "6") (pinfunction "O1_6") (pintype "passive"))
      (node (ref "IC4") (pin "13") (pinfunction "I_13") (pintype "input"))
      (node (ref "IC4") (pin "6") (pinfunction "O_6") (pintype "open_collector"))
      (node (ref "R26") (pin "1") (pinfunction "1_1") (pintype "passive"))
    )
    (net (code "44") (name "Net-(D4-I1)") (class "Default")
      (node (ref "D4") (pin "3") (pinfunction "I1_3") (pintype "passive"))
      (node (ref "J1") (pin "4") (pinfunction "4_4") (pintype "passive"))
    )
    (net (code "45") (name "Net-(D4-O2)") (class "Default")
      (node (ref "D4") (pin "1") (pinfunction "O2_1") (pintype "passive"))
      (node (ref "IC4") (pin "2") (pinfunction "O_2") (pintype "open_collector"))
      (node (ref "IC4") (pin "3") (pinfunction "I_3") (pintype "input"))
      (node (ref "R35") (pin "1") (pinfunction "1_1") (pintype "passive"))
    )
    (net (code "46") (name "Net-(IC2-DO+)") (class "Default")
      (node (ref "IC2") (pin "6") (pinfunction "DO+_6") (pintype "output"))
      (node (ref "J1") (pin "1") (pinfunction "1_1") (pintype "passive"))
    )
    (net (code "47") (name "Net-(IC2-DO-)") (class "Default")
      (node (ref "IC2") (pin "5") (pinfunction "DO-_5") (pintype "output"))
      (node (ref "J1") (pin "2") (pinfunction "2_2") (pintype "passive"))
    )
    (net (code "48") (name "Net-(IC2-RI+)") (class "Default")
      (node (ref "IC2") (pin "8") (pinfunction "RI+_8") (pintype "input"))
      (node (ref "J1") (pin "3") (pinfunction "3_3") (pintype "passive"))
      (node (ref "R15") (pin "1") (pinfunction "1_1") (pintype "passive"))
      (node (ref "R16") (pin "1") (pinfunction "1_1") (pintype "passive"))
    )
    (net (code "49") (name "Net-(IC2-RI-)") (class "Default")
      (node (ref "IC2") (pin "7") (pinfunction "RI-_7") (pintype "input"))
      (node (ref "J1") (pin "6") (pinfunction "6_6") (pintype "passive"))
      (node (ref "R14") (pin "1") (pinfunction "1_1") (pintype "passive"))
      (node (ref "R16") (pin "2") (pinfunction "2_2") (pintype "passive"))
    )
    (net (code "50") (name "Net-(IC3-RBIAS)") (class "Default")
      (node (ref "IC3") (pin "24") (pinfunction "RBIAS_24") (pintype "bidirectional"))
      (node (ref "R17") (pin "2") (pinfunction "2_2") (pintype "passive"))
    )
    (net (code "51") (name "Net-(IC3-REFCLKO{slash}~{INT})") (class "Default")
      (node (ref "IC3") (pin "14") (pinfunction "REFCLKO/~{INT}_14") (pintype "bidirectional"))
      (node (ref "R22") (pin "2") (pinfunction "2_2") (pintype "passive"))
    )
    (net (code "52") (name "Net-(IC3-RXN)") (class "Default")
      (node (ref "IC3") (pin "22") (pinfunction "RXN_22") (pintype "bidirectional"))
      (node (ref "R19") (pin "2") (pinfunction "2_2") (pintype "passive"))
      (node (ref "T1") (pin "6") (pinfunction "RD-_6") (pintype "passive"))
    )
    (net (code "53") (name "Net-(IC3-RXP)") (class "Default")
      (node (ref "IC3") (pin "23") (pinfunction "RXP_23") (pintype "bidirectional"))
      (node (ref "R18") (pin "2") (pinfunction "2_2") (pintype "passive"))
      (node (ref "T1") (pin "3") (pinfunction "RD+_3") (pintype "passive"))
    )
    (net (code "54") (name "Net-(IC3-TXN)") (class "Default")
      (node (ref "IC3") (pin "20") (pinfunction "TXN_20") (pintype "bidirectional"))
      (node (ref "R20") (pin "2") (pinfunction "2_2") (pintype "passive"))
      (node (ref "T1") (pin "2") (pinfunction "TD-_2") (pintype "passive"))
    )
    (net (code "55") (name "Net-(IC3-TXP)") (class "Default")
      (node (ref "IC3") (pin "21") (pinfunction "TXP_21") (pintype "bidirectional"))
      (node (ref "R21") (pin "2") (pinfunction "2_2") (pintype "passive"))
      (node (ref "T1") (pin "1") (pinfunction "TD+_1") (pintype "passive"))
    )
    (net (code "56") (name "Net-(IC3-VDDCR)") (class "Default")
      (node (ref "C23") (pin "1") (pinfunction "1_1") (pintype "passive"))
      (node (ref "C8") (pin "+") (pinfunction "+_+") (pintype "passive"))
      (node (ref "IC3") (pin "6") (pinfunction "VDDCR_6") (pintype "power_in"))
    )
    (net (code "57") (name "Net-(IC4D-I)") (class "Default")
      (node (ref "IC4") (pin "10") (pinfunction "O_10") (pintype "open_collector"))
      (node (ref "IC4") (pin "9") (pinfunction "I_9") (pintype "input"))
      (node (ref "R28") (pin "1") (pinfunction "1_1") (pintype "passive"))
    )
    (net (code "58") (name "Net-(IC5-CAPMINUS)") (class "Default")
      (node (ref "C16") (pin "2") (pinfunction "2_2") (pintype "passive"))
      (node (ref "IC5") (pin "23") (pinfunction "CAPMINUS_23") (pintype "passive"))
    )
    (net (code "59") (name "Net-(IC5-LINKOUT)") (class "Default")
      (node (ref "IC5") (pin "1") (pinfunction "LINKOUT_1") (pintype "output"))
      (node (ref "R30") (pin "2") (pinfunction "2_2") (pintype "passive"))
    )
    (net (code "60") (name "Net-(IC7-+VOUT)") (class "Default")
      (node (ref "IC7") (pin "6") (pinfunction "+VOUT_6") (pintype "passive"))
      (node (ref "J2") (pin "2") (pinfunction "S_2") (pintype "passive"))
      (node (ref "J3") (pin "2") (pinfunction "S_2") (pintype "passive"))
    )
    (net (code "61") (name "Net-(IC8-PIO0_25)") (class "Default")
      (node (ref "IC8") (pin "40") (pinfunction "PIO0_25_40") (pintype "tri_state"))
      (node (ref "TP2") (pin "P$1") (pinfunction "P$1_P$1") (pintype "passive"))
    )
    (net (code "62") (name "Net-(IC8-XTALIN)") (class "Default")
      (node (ref "C22") (pin "2") (pinfunction "2_2") (pintype "passive"))
      (node (ref "IC8") (pin "20") (pinfunction "XTALIN_20") (pintype "tri_state"))
      (node (ref "Q1") (pin "2") (pinfunction "2_2") (pintype "passive"))
    )
    (net (code "63") (name "Net-(IC8-XTALOUT)") (class "Default")
      (node (ref "C21") (pin "2") (pinfunction "2_2") (pintype "passive"))
      (node (ref "IC8") (pin "19") (pinfunction "XTALOUT_19") (pintype "tri_state"))
      (node (ref "Q1") (pin "1") (pinfunction "1_1") (pintype "passive"))
    )
    (net (code "64") (name "Net-(IC9-IN--Pad14)") (class "Default")
      (node (ref "IC9") (pin "14") (pinfunction "IN-_14") (pintype "passive"))
      (node (ref "IC9") (pin "15") (pinfunction "IN-_15") (pintype "passive"))
      (node (ref "IC9") (pin "16") (pinfunction "IN-_16") (pintype "passive"))
      (node (ref "SCREW1") (pin "P$1") (pinfunction "P$1_P$1") (pintype "bidirectional"))
      (node (ref "SCREW3") (pin "P$1") (pinfunction "P$1_P$1") (pintype "bidirectional"))
      (node (ref "SV100") (pin "22") (pinfunction "22_22") (pintype "passive"))
      (node (ref "SV100") (pin "24") (pinfunction "24_24") (pintype "passive"))
      (node (ref "SV100") (pin "26") (pinfunction "26_26") (pintype "passive"))
      (node (ref "SV100") (pin "28") (pinfunction "28_28") (pintype "passive"))
      (node (ref "SV100") (pin "30") (pinfunction "30_30") (pintype "passive"))
      (node (ref "SV100") (pin "31") (pinfunction "31_31") (pintype "passive"))
      (node (ref "SV100") (pin "32") (pinfunction "32_32") (pintype "passive"))
      (node (ref "SV100") (pin "33") (pinfunction "33_33") (pintype "passive"))
      (node (ref "SV100") (pin "34") (pinfunction "34_34") (pintype "passive"))
      (node (ref "SV100") (pin "35") (pinfunction "35_35") (pintype "passive"))
      (node (ref "SV100") (pin "36") (pinfunction "36_36") (pintype "passive"))
      (node (ref "SV100") (pin "37") (pinfunction "37_37") (pintype "passive"))
      (node (ref "SV100") (pin "38") (pinfunction "38_38") (pintype "passive"))
      (node (ref "SV100") (pin "39") (pinfunction "39_39") (pintype "passive"))
      (node (ref "SV100") (pin "40") (pinfunction "40_40") (pintype "passive"))
    )
    (net (code "65") (name "Net-(IC10A-O)") (class "Default")
      (node (ref "IC10") (pin "13") (pinfunction "I1_13") (pintype "input"))
      (node (ref "IC10") (pin "3") (pinfunction "O_3") (pintype "output"))
    )
    (net (code "66") (name "Net-(IC10C-O)") (class "Default")
      (node (ref "IC10") (pin "12") (pinfunction "I0_12") (pintype "input"))
      (node (ref "IC10") (pin "8") (pinfunction "O_8") (pintype "output"))
    )
    (net (code "67") (name "Net-(IC10D-O)") (class "Default")
      (node (ref "IC10") (pin "11") (pinfunction "O_11") (pintype "output"))
      (node (ref "IC5") (pin "21") (pinfunction "NOTCS_21") (pintype "input"))
    )
    (net (code "68") (name "Net-(LED1-PadC)") (class "Default")
      (node (ref "LED1") (pin "C") (pinfunction "C_C") (pintype "passive"))
      (node (ref "R1") (pin "2") (pinfunction "2_2") (pintype "passive"))
    )
    (net (code "69") (name "Net-(LED2-PadC)") (class "Default")
      (node (ref "LED2") (pin "C") (pinfunction "C_C") (pintype "passive"))
      (node (ref "R29") (pin "2") (pinfunction "2_2") (pintype "passive"))
    )
    (net (code "70") (name "Net-(R31-Pad2)") (class "Default")
      (node (ref "R31") (pin "2") (pinfunction "2_2") (pintype "passive"))
      (node (ref "SP1") (pin "2") (pinfunction "2_2") (pintype "passive"))
    )
    (net (code "71") (name "Net-(T1-LED1_G+)") (class "Default")
      (node (ref "R13") (pin "1") (pinfunction "1_1") (pintype "passive"))
      (node (ref "T1") (pin "9") (pinfunction "LED1_G+_9") (pintype "passive"))
    )
    (net (code "72") (name "Net-(T1-LED2_Y-)") (class "Default")
      (node (ref "R11") (pin "1") (pinfunction "1_1") (pintype "passive"))
      (node (ref "T1") (pin "11") (pinfunction "LED2_Y-_11") (pintype "passive"))
    )
    (net (code "73") (name "OUT0") (class "Default")
      (node (ref "IC5") (pin "2") (pinfunction "LINKIN_2") (pintype "input"))
      (node (ref "SV100") (pin "27") (pinfunction "27_27") (pintype "passive"))
    )
    (net (code "74") (name "OUT1") (class "Default")
      (node (ref "IC2") (pin "3") (pinfunction "DI_3") (pintype "input"))
      (node (ref "SV100") (pin "23") (pinfunction "23_23") (pintype "passive"))
    )
    (net (code "75") (name "OUTINT") (class "Default")
      (node (ref "IC5") (pin "4") (pinfunction "OUTPUTINT_4") (pintype "output"))
      (node (ref "IC8") (pin "43") (pinfunction "PIO1_22_43") (pintype "tri_state"))
    )
    (net (code "76") (name "PON") (class "Default")
      (node (ref "IC6") (pin "2") (pinfunction "IN_2") (pintype "input"))
      (node (ref "IC8") (pin "93") (pinfunction "PIO0_0_93") (pintype "tri_state"))
      (node (ref "R23") (pin "2") (pinfunction "2_2") (pintype "passive"))
    )
    (net (code "77") (name "RD") (class "Default")
      (node (ref "IC10") (pin "10") (pinfunction "I1_10") (pintype "input"))
      (node (ref "IC8") (pin "70") (pinfunction "PIO0_17_70") (pintype "tri_state"))
    )
    (net (code "78") (name "RESETIN") (class "Default")
      (node (ref "IC4") (pin "4") (pinfunction "O_4") (pintype "open_collector"))
      (node (ref "R34") (pin "1") (pinfunction "1_1") (pintype "passive"))
      (node (ref "SV100") (pin "17") (pinfunction "17_17") (pintype "passive"))
    )
    (net (code "79") (name "RESETOUT") (class "Default")
      (node (ref "IC4") (pin "1") (pinfunction "I_1") (pintype "input"))
      (node (ref "IC8") (pin "3") (pinfunction "PIO1_4_3") (pintype "tri_state"))
    )
    (net (code "80") (name "RES_012") (class "Default")
      (node (ref "IC5") (pin "11") (pinfunction "RESET_11") (pintype "input"))
      (node (ref "IC8") (pin "82") (pinfunction "PIO0_29_82") (pintype "tri_state"))
      (node (ref "R10") (pin "1") (pinfunction "1_1") (pintype "passive"))
    )
    (net (code "81") (name "RES_UP") (class "Default")
      (node (ref "CON2") (pin "10") (pinfunction "10_10") (pintype "passive"))
      (node (ref "IC8") (pin "48") (pinfunction "RESET_48") (pintype "tri_state"))
    )
    (net (code "82") (name "SCL") (class "Default")
      (node (ref "IC8") (pin "69") (pinfunction "PIO0_14*_69") (pintype "tri_state"))
      (node (ref "IC9") (pin "9") (pinfunction "SCL_9") (pintype "bidirectional"))
      (node (ref "J4") (pin "4") (pinfunction "S_4") (pintype "passive"))
      (node (ref "R6") (pin "1") (pinfunction "1_1") (pintype "passive"))
    )
    (net (code "83") (name "SDA") (class "Default")
      (node (ref "IC8") (pin "67") (pinfunction "PIO0_13*_67") (pintype "tri_state"))
      (node (ref "IC9") (pin "8") (pinfunction "SDA_8") (pintype "bidirectional"))
      (node (ref "J4") (pin "3") (pinfunction "S_3") (pintype "passive"))
      (node (ref "R5") (pin "1") (pinfunction "1_1") (pintype "passive"))
    )
    (net (code "84") (name "SPEAKER") (class "Default")
      (node (ref "IC8") (pin "28") (pinfunction "PIO0_31_28") (pintype "tri_state"))
      (node (ref "R31") (pin "1") (pinfunction "1_1") (pintype "passive"))
    )
    (net (code "85") (name "SWCLK") (class "Default")
      (node (ref "CON2") (pin "4") (pinfunction "4_4") (pintype "passive"))
      (node (ref "IC8") (pin "24") (pinfunction "PIO0_11_24") (pintype "tri_state"))
    )
    (net (code "86") (name "SWDIO") (class "Default")
      (node (ref "CON2") (pin "2") (pinfunction "2_2") (pintype "passive"))
      (node (ref "IC8") (pin "25") (pinfunction "PIO0_12_25") (pintype "tri_state"))
    )
    (net (code "87") (name "SWO") (class "Default")
      (node (ref "CON2") (pin "6") (pinfunction "6_6") (pintype "passive"))
      (node (ref "IC8") (pin "23") (pinfunction "PIO0_10_23") (pintype "tri_state"))
    )
    (net (code "88") (name "TEST") (class "Default")
      (node (ref "IC8") (pin "5") (pinfunction "PIO1_18_5") (pintype "tri_state"))
      (node (ref "SV100") (pin "11") (pinfunction "11_11") (pintype "passive"))
    )
    (net (code "89") (name "VCC") (class "Default")
      (node (ref "C1") (pin "+") (pinfunction "+_+") (pintype "passive"))
      (node (ref "C12") (pin "1") (pinfunction "1_1") (pintype "passive"))
      (node (ref "C16") (pin "1") (pinfunction "1_1") (pintype "passive"))
      (node (ref "C19") (pin "1") (pinfunction "1_1") (pintype "passive"))
      (node (ref "C2") (pin "1") (pinfunction "1_1") (pintype "passive"))
      (node (ref "C20") (pin "1") (pinfunction "1_1") (pintype "passive"))
      (node (ref "CON1") (pin "2") (pinfunction "2_2") (pintype "passive"))
      (node (ref "D3") (pin "5") (pinfunction "VCC_5") (pintype "passive"))
      (node (ref "D4") (pin "5") (pinfunction "VCC_5") (pintype "passive"))
      (node (ref "IC1") (pin "3") (pinfunction "IN_3") (pintype "input"))
      (node (ref "IC4") (pin "14") (pinfunction "VCC_14") (pintype "power_in"))
      (node (ref "IC5") (pin "24") (pinfunction "VCC_24") (pintype "power_in"))
      (node (ref "IC6") (pin "6") (pinfunction "VBB_6") (pintype "passive"))
      (node (ref "IC9") (pin "10") (pinfunction "VS_10") (pintype "power_in"))
      (node (ref "IC9") (pin "12") (pinfunction "VBUS_12") (pintype "passive"))
      (node (ref "J4") (pin "5") (pinfunction "S_5") (pintype "passive"))
      (node (ref "LED1") (pin "A") (pinfunction "A_A") (pintype "passive"))
      (node (ref "R14") (pin "2") (pinfunction "2_2") (pintype "passive"))
      (node (ref "R2") (pin "2") (pinfunction "2_2") (pintype "passive"))
      (node (ref "R26") (pin "2") (pinfunction "2_2") (pintype "passive"))
      (node (ref "R28") (pin "2") (pinfunction "2_2") (pintype "passive"))
      (node (ref "R3") (pin "2") (pinfunction "2_2") (pintype "passive"))
      (node (ref "R32") (pin "2") (pinfunction "2_2") (pintype "passive"))
      (node (ref "R35") (pin "2") (pinfunction "2_2") (pintype "passive"))
      (node (ref "R5") (pin "2") (pinfunction "2_2") (pintype "passive"))
      (node (ref "R6") (pin "2") (pinfunction "2_2") (pintype "passive"))
    )
    (net (code "90") (name "VCCINT") (class "Default")
      (node (ref "C4") (pin "1") (pinfunction "1_1") (pintype "passive"))
      (node (ref "IC2") (pin "1") (pinfunction "VCC_1") (pintype "power_in"))
      (node (ref "IC6") (pin "5") (pinfunction "OUT_5") (pintype "power_in"))
      (node (ref "IC7") (pin "2") (pinfunction "+VIN_2") (pintype "passive"))
      (node (ref "IC9") (pin "1") (pinfunction "IN+_1") (pintype "passive"))
      (node (ref "IC9") (pin "2") (pinfunction "IN+_2") (pintype "passive"))
      (node (ref "IC9") (pin "3") (pinfunction "IN+_3") (pintype "passive"))
      (node (ref "LED2") (pin "A") (pinfunction "A_A") (pintype "passive"))
      (node (ref "R24") (pin "2") (pinfunction "2_2") (pintype "passive"))
      (node (ref "R34") (pin "2") (pinfunction "2_2") (pintype "passive"))
    )
    (net (code "91") (name "VCCIO") (class "Default")
      (node (ref "C10") (pin "2") (pinfunction "2_2") (pintype "passive"))
      (node (ref "C5") (pin "+") (pinfunction "+_+") (pintype "passive"))
      (node (ref "C7") (pin "1") (pinfunction "1_1") (pintype "passive"))
      (node (ref "C9") (pin "1") (pinfunction "1_1") (pintype "passive"))
      (node (ref "IC3") (pin "1") (pinfunction "VDD2A_1") (pintype "power_in"))
      (node (ref "IC3") (pin "19") (pinfunction "VDD1A_19") (pintype "power_in"))
      (node (ref "L1") (pin "2") (pinfunction "2_2") (pintype "passive"))
      (node (ref "R18") (pin "1") (pinfunction "1_1") (pintype "passive"))
      (node (ref "R19") (pin "1") (pinfunction "1_1") (pintype "passive"))
      (node (ref "R20") (pin "1") (pinfunction "1_1") (pintype "passive"))
      (node (ref "R21") (pin "1") (pinfunction "1_1") (pintype "passive"))
      (node (ref "T1") (pin "4") (pinfunction "CTD_4") (pintype "passive"))
      (node (ref "T1") (pin "5") (pinfunction "CRD_5") (pintype "passive"))
    )
    (net (code "92") (name "VDD") (class "Default")
      (node (ref "C11") (pin "1") (pinfunction "1_1") (pintype "passive"))
      (node (ref "C13") (pin "1") (pinfunction "1_1") (pintype "passive"))
      (node (ref "C14") (pin "1") (pinfunction "1_1") (pintype "passive"))
      (node (ref "C15") (pin "1") (pinfunction "1_1") (pintype "passive"))
      (node (ref "C17") (pin "1") (pinfunction "1_1") (pintype "passive"))
      (node (ref "C18") (pin "1") (pinfunction "1_1") (pintype "passive"))
      (node (ref "C3") (pin "+") (pinfunction "+_+") (pintype "passive"))
      (node (ref "C6") (pin "1") (pinfunction "1_1") (pintype "passive"))
      (node (ref "CON2") (pin "1") (pinfunction "1_1") (pintype "passive"))
      (node (ref "IC1") (pin "2") (pinfunction "OUT_2") (pintype "passive"))
      (node (ref "IC10") (pin "14") (pinfunction "VCC_14") (pintype "power_in"))
      (node (ref "IC3") (pin "9") (pinfunction "VDDIO_9") (pintype "power_in"))
      (node (ref "IC8") (pin "1") (pinfunction "VCC_1") (pintype "power_in"))
      (node (ref "IC8") (pin "10") (pinfunction "USB1_AVDDC3V3_10") (pintype "tri_state"))
      (node (ref "IC8") (pin "11") (pinfunction "USB1_AVDDTX3V3_11") (pintype "tri_state"))
      (node (ref "IC8") (pin "21") (pinfunction "VCC_21") (pintype "power_in"))
      (node (ref "IC8") (pin "31") (pinfunction "VREFP_31") (pintype "tri_state"))
      (node (ref "IC8") (pin "32") (pinfunction "VCCA_32") (pintype "power_in"))
      (node (ref "IC8") (pin "33") (pinfunction "VCC_33") (pintype "power_in"))
      (node (ref "IC8") (pin "45") (pinfunction "VBAT_45") (pintype "tri_state"))
      (node (ref "IC8") (pin "50") (pinfunction "VCC_50") (pintype "power_in"))
      (node (ref "IC8") (pin "54") (pinfunction "VCC_54") (pintype "power_in"))
      (node (ref "IC8") (pin "75") (pinfunction "VCC_75") (pintype "power_in"))
      (node (ref "IC8") (pin "76") (pinfunction "VCC_76") (pintype "power_in"))
      (node (ref "IC8") (pin "9") (pinfunction "USB1_VBUS_9") (pintype "tri_state"))
      (node (ref "IC8") (pin "99") (pinfunction "VCC_99") (pintype "power_in"))
      (node (ref "L1") (pin "1") (pinfunction "1_1") (pintype "passive"))
      (node (ref "R10") (pin "2") (pinfunction "2_2") (pintype "passive"))
      (node (ref "R25") (pin "1") (pinfunction "1_1") (pintype "passive"))
      (node (ref "R4") (pin "2") (pinfunction "2_2") (pintype "passive"))
      (node (ref "R7") (pin "2") (pinfunction "2_2") (pintype "passive"))
      (node (ref "R8") (pin "2") (pinfunction "2_2") (pintype "passive"))
      (node (ref "R9") (pin "2") (pinfunction "2_2") (pintype "passive"))
    )
    (net (code "93") (name "WR") (class "Default")
      (node (ref "IC10") (pin "9") (pinfunction "I0_9") (pintype "input"))
      (node (ref "IC5") (pin "3") (pinfunction "RNOTW_3") (pintype "input"))
      (node (ref "IC8") (pin "26") (pinfunction "PIO0_15_26") (pintype "tri_state"))
    )
    (net (code "94") (name "unconnected-(CON2-Pad7)") (class "Default")
      (node (ref "CON2") (pin "7") (pinfunction "7_7") (pintype "passive"))
    )
    (net (code "95") (name "unconnected-(CON2-Pad8)") (class "Default")
      (node (ref "CON2") (pin "8") (pinfunction "8_8") (pintype "passive"))
    )
    (net (code "96") (name "unconnected-(D4-I2-Pad4)") (class "Default")
      (node (ref "D4") (pin "4") (pinfunction "I2_4") (pintype "passive"))
    )
    (net (code "97") (name "unconnected-(D4-O1-Pad6)") (class "Default")
      (node (ref "D4") (pin "6") (pinfunction "O1_6") (pintype "passive"))
    )
    (net (code "98") (name "unconnected-(IC3-RXER{slash}PHYAD0-Pad10)") (class "Default")
      (node (ref "IC3") (pin "10") (pinfunction "RXER/PHYAD0_10") (pintype "bidirectional"))
    )
    (net (code "99") (name "unconnected-(IC3-XTAL2-Pad4)") (class "Default")
      (node (ref "IC3") (pin "4") (pinfunction "XTAL2_4") (pintype "bidirectional"))
    )
    (net (code "100") (name "unconnected-(IC8-PIO0_23-Pad35)") (class "Default")
      (node (ref "IC8") (pin "35") (pinfunction "PIO0_23_35") (pintype "tri_state"))
    )
    (net (code "101") (name "unconnected-(IC8-PIO0_24-Pad38)") (class "Default")
      (node (ref "IC8") (pin "38") (pinfunction "PIO0_24_38") (pintype "tri_state"))
    )
    (net (code "102") (name "unconnected-(IC8-PIO0_26-Pad56)") (class "Default")
      (node (ref "IC8") (pin "56") (pinfunction "PIO0_26_56") (pintype "tri_state"))
    )
    (net (code "103") (name "unconnected-(IC8-PIO0_28-Pad44)") (class "Default")
      (node (ref "IC8") (pin "44") (pinfunction "PIO0_28_44") (pintype "tri_state"))
    )
    (net (code "104") (name "unconnected-(IC8-PIO0_30-Pad95)") (class "Default")
      (node (ref "IC8") (pin "95") (pinfunction "PIO0_30_95") (pintype "tri_state"))
    )
    (net (code "105") (name "unconnected-(IC8-PIO1_0-Pad29)") (class "Default")
      (node (ref "IC8") (pin "29") (pinfunction "PIO1_0_29") (pintype "tri_state"))
    )
    (net (code "106") (name "unconnected-(IC8-PIO1_1-Pad55)") (class "Default")
      (node (ref "IC8") (pin "55") (pinfunction "PIO1_1_55") (pintype "tri_state"))
    )
    (net (code "107") (name "unconnected-(IC8-PIO1_2-Pad58)") (class "Default")
      (node (ref "IC8") (pin "58") (pinfunction "PIO1_2_58") (pintype "tri_state"))
    )
    (net (code "108") (name "unconnected-(IC8-PIO1_3-Pad60)") (class "Default")
      (node (ref "IC8") (pin "60") (pinfunction "PIO1_3_60") (pintype "tri_state"))
    )
    (net (code "109") (name "unconnected-(IC8-PIO1_7-Pad18)") (class "Default")
      (node (ref "IC8") (pin "18") (pinfunction "PIO1_7_18") (pintype "tri_state"))
    )
    (net (code "110") (name "unconnected-(IC8-PIO1_8-Pad36)") (class "Default")
      (node (ref "IC8") (pin "36") (pinfunction "PIO1_8_36") (pintype "tri_state"))
    )
    (net (code "111") (name "unconnected-(IC8-PIO1_19-Pad16)") (class "Default")
      (node (ref "IC8") (pin "16") (pinfunction "PIO1_19_16") (pintype "tri_state"))
    )
    (net (code "112") (name "unconnected-(IC8-PIO1_20-Pad17)") (class "Default")
      (node (ref "IC8") (pin "17") (pinfunction "PIO1_20_17") (pintype "tri_state"))
    )
    (net (code "113") (name "unconnected-(IC8-PIO1_21-Pad37)") (class "Default")
      (node (ref "IC8") (pin "37") (pinfunction "PIO1_21_37") (pintype "tri_state"))
    )
    (net (code "114") (name "unconnected-(IC8-PIO1_23-Pad46)") (class "Default")
      (node (ref "IC8") (pin "46") (pinfunction "PIO1_23_46") (pintype "tri_state"))
    )
    (net (code "115") (name "unconnected-(IC8-PIO1_25-Pad59)") (class "Default")
      (node (ref "IC8") (pin "59") (pinfunction "PIO1_25_59") (pintype "tri_state"))
    )
    (net (code "116") (name "unconnected-(IC8-PIO1_26-Pad63)") (class "Default")
      (node (ref "IC8") (pin "63") (pinfunction "PIO1_26_63") (pintype "tri_state"))
    )
    (net (code "117") (name "unconnected-(IC8-PIO1_28-Pad73)") (class "Default")
      (node (ref "IC8") (pin "73") (pinfunction "PIO1_28_73") (pintype "tri_state"))
    )
    (net (code "118") (name "unconnected-(IC8-PIO1_30-Pad86)") (class "Default")
      (node (ref "IC8") (pin "86") (pinfunction "PIO1_30_86") (pintype "tri_state"))
    )
    (net (code "119") (name "unconnected-(IC8-RTCXOUT-Pad52)") (class "Default")
      (node (ref "IC8") (pin "52") (pinfunction "RTCXOUT_52") (pintype "tri_state"))
    )
    (net (code "120") (name "unconnected-(IC8-USB0_DM-Pad98)") (class "Default")
      (node (ref "IC8") (pin "98") (pinfunction "USB0_DM_98") (pintype "tri_state"))
    )
    (net (code "121") (name "unconnected-(IC8-USB0_DP-Pad97)") (class "Default")
      (node (ref "IC8") (pin "97") (pinfunction "USB0_DP_97") (pintype "tri_state"))
    )
    (net (code "122") (name "unconnected-(IC8-USB1_DM-Pad12)") (class "Default")
      (node (ref "IC8") (pin "12") (pinfunction "USB1_DM_12") (pintype "tri_state"))
    )
    (net (code "123") (name "unconnected-(IC8-USB1_DP-Pad13)") (class "Default")
      (node (ref "IC8") (pin "13") (pinfunction "USB1_DP_13") (pintype "tri_state"))
    )
    (net (code "124") (name "unconnected-(IC8-USB1_ID-Pad8)") (class "Default")
      (node (ref "IC8") (pin "8") (pinfunction "USB1_ID_8") (pintype "tri_state"))
    )
    (net (code "125") (name "unconnected-(IC8-USB1_REXT-Pad7)") (class "Default")
      (node (ref "IC8") (pin "7") (pinfunction "USB1_REXT_7") (pintype "tri_state"))
    )
    (net (code "126") (name "unconnected-(IC9-ALERT-Pad7)") (class "Default")
      (node (ref "IC9") (pin "7") (pinfunction "ALERT_7") (pintype "output"))
    )
    (net (code "127") (name "unconnected-(IC10B-O-Pad6)") (class "Default")
      (node (ref "IC10") (pin "6") (pinfunction "O_6") (pintype "output"))
    )
    (net (code "128") (name "unconnected-(T1-NC-Pad7)") (class "Default")
      (node (ref "T1") (pin "7") (pinfunction "NC_7") (pintype "passive"))
    )
  )
)
